# amebot_sensors.net
KiCad netlist of a schematic drawn in EAGLE
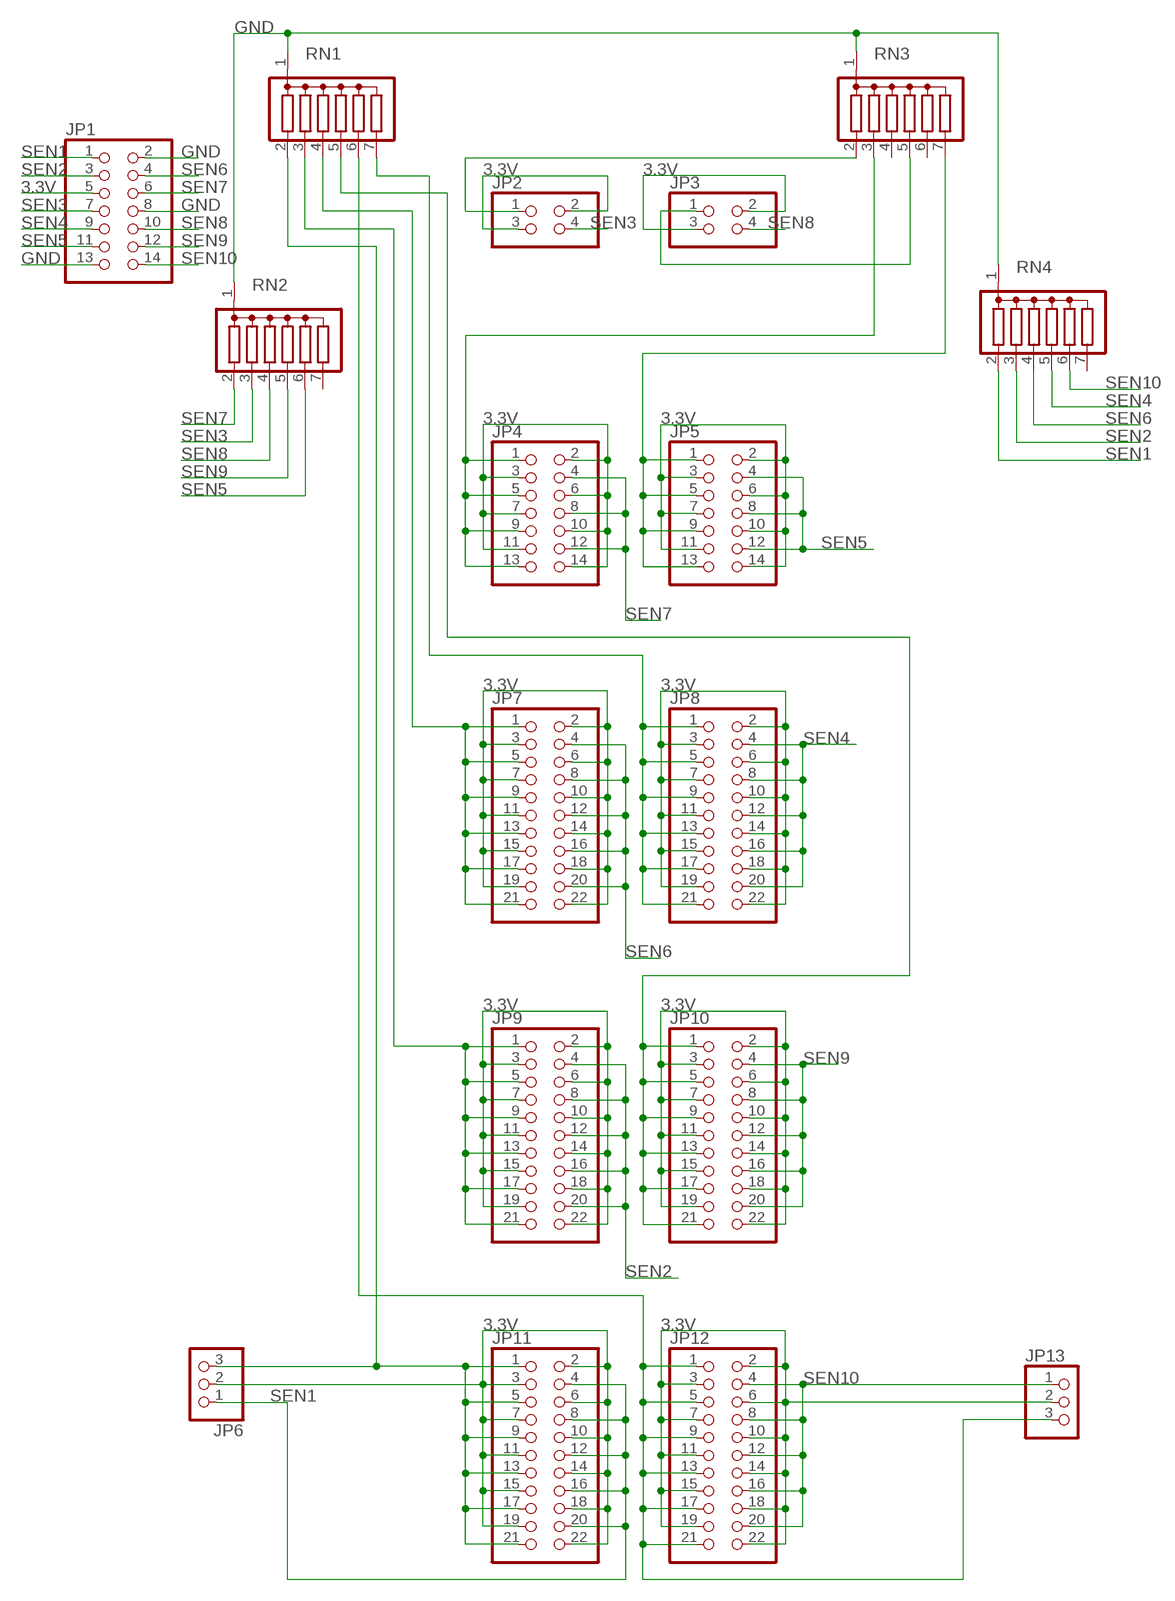
[diagram p0: schematic, sheet 1]

(export (version "E")
  (design (tool "Eeschema 10.0.6"))
  (components
    (comp (ref "JP1")
      (value "PINHD-2X7")
      (footprint "eagle-import:2X07")
      (libsource (lib "eagle-import") (part "PINHD-2X7"))
    )
    (comp (ref "JP2")
      (value "PINHD-2X2")
      (footprint "eagle-import:2X02")
      (libsource (lib "eagle-import") (part "PINHD-2X2"))
    )
    (comp (ref "JP3")
      (value "PINHD-2X2")
      (footprint "eagle-import:2X02")
      (libsource (lib "eagle-import") (part "PINHD-2X2"))
    )
    (comp (ref "JP4")
      (value "PINHD-2X7")
      (footprint "eagle-import:2X07")
      (libsource (lib "eagle-import") (part "PINHD-2X7"))
    )
    (comp (ref "JP5")
      (value "PINHD-2X7")
      (footprint "eagle-import:2X07")
      (libsource (lib "eagle-import") (part "PINHD-2X7"))
    )
    (comp (ref "JP6")
      (value "PINHD-1X3")
      (footprint "eagle-import:1X03")
      (libsource (lib "eagle-import") (part "PINHD-1X3"))
    )
    (comp (ref "JP7")
      (value "PINHD-2X11")
      (footprint "eagle-import:2X11")
      (libsource (lib "eagle-import") (part "PINHD-2X11"))
    )
    (comp (ref "JP8")
      (value "PINHD-2X11")
      (footprint "eagle-import:2X11")
      (libsource (lib "eagle-import") (part "PINHD-2X11"))
    )
    (comp (ref "JP9")
      (value "PINHD-2X11")
      (footprint "eagle-import:2X11")
      (libsource (lib "eagle-import") (part "PINHD-2X11"))
    )
    (comp (ref "JP10")
      (value "PINHD-2X11")
      (footprint "eagle-import:2X11")
      (libsource (lib "eagle-import") (part "PINHD-2X11"))
    )
    (comp (ref "JP11")
      (value "PINHD-2X11")
      (footprint "eagle-import:2X11")
      (libsource (lib "eagle-import") (part "PINHD-2X11"))
    )
    (comp (ref "JP12")
      (value "PINHD-2X11")
      (footprint "eagle-import:2X11")
      (libsource (lib "eagle-import") (part "PINHD-2X11"))
    )
    (comp (ref "JP13")
      (value "PINHD-1X3")
      (footprint "eagle-import:1X03")
      (libsource (lib "eagle-import") (part "PINHD-1X3"))
    )
    (comp (ref "RN1")
      (value "G06R")
      (footprint "eagle-import:SIL7")
      (libsource (lib "eagle-import") (part "G06R"))
    )
    (comp (ref "RN2")
      (value "G06R")
      (footprint "eagle-import:SIL7")
      (libsource (lib "eagle-import") (part "G06R"))
    )
    (comp (ref "RN3")
      (value "G06R")
      (footprint "eagle-import:SIL7")
      (libsource (lib "eagle-import") (part "G06R"))
    )
    (comp (ref "RN4")
      (value "G06R")
      (footprint "eagle-import:SIL7")
      (libsource (lib "eagle-import") (part "G06R"))
    )
  )
  (nets
    (net (code "1") (name "/3.3V") (class "Default")
      (node (ref "JP1") (pin "5") (pinfunction "5_5") (pintype "passive"))
      (node (ref "JP10") (pin "10") (pinfunction "10_10") (pintype "passive"))
      (node (ref "JP10") (pin "11") (pinfunction "11_11") (pintype "passive"))
      (node (ref "JP10") (pin "14") (pinfunction "14_14") (pintype "passive"))
      (node (ref "JP10") (pin "15") (pinfunction "15_15") (pintype "passive"))
      (node (ref "JP10") (pin "18") (pinfunction "18_18") (pintype "passive"))
      (node (ref "JP10") (pin "19") (pinfunction "19_19") (pintype "passive"))
      (node (ref "JP10") (pin "2") (pinfunction "2_2") (pintype "passive"))
      (node (ref "JP10") (pin "22") (pinfunction "22_22") (pintype "passive"))
      (node (ref "JP10") (pin "3") (pinfunction "3_3") (pintype "passive"))
      (node (ref "JP10") (pin "6") (pinfunction "6_6") (pintype "passive"))
      (node (ref "JP10") (pin "7") (pinfunction "7_7") (pintype "passive"))
      (node (ref "JP11") (pin "10") (pinfunction "10_10") (pintype "passive"))
      (node (ref "JP11") (pin "11") (pinfunction "11_11") (pintype "passive"))
      (node (ref "JP11") (pin "14") (pinfunction "14_14") (pintype "passive"))
      (node (ref "JP11") (pin "15") (pinfunction "15_15") (pintype "passive"))
      (node (ref "JP11") (pin "18") (pinfunction "18_18") (pintype "passive"))
      (node (ref "JP11") (pin "19") (pinfunction "19_19") (pintype "passive"))
      (node (ref "JP11") (pin "2") (pinfunction "2_2") (pintype "passive"))
      (node (ref "JP11") (pin "22") (pinfunction "22_22") (pintype "passive"))
      (node (ref "JP11") (pin "3") (pinfunction "3_3") (pintype "passive"))
      (node (ref "JP11") (pin "6") (pinfunction "6_6") (pintype "passive"))
      (node (ref "JP11") (pin "7") (pinfunction "7_7") (pintype "passive"))
      (node (ref "JP12") (pin "10") (pinfunction "10_10") (pintype "passive"))
      (node (ref "JP12") (pin "11") (pinfunction "11_11") (pintype "passive"))
      (node (ref "JP12") (pin "14") (pinfunction "14_14") (pintype "passive"))
      (node (ref "JP12") (pin "15") (pinfunction "15_15") (pintype "passive"))
      (node (ref "JP12") (pin "18") (pinfunction "18_18") (pintype "passive"))
      (node (ref "JP12") (pin "19") (pinfunction "19_19") (pintype "passive"))
      (node (ref "JP12") (pin "2") (pinfunction "2_2") (pintype "passive"))
      (node (ref "JP12") (pin "22") (pinfunction "22_22") (pintype "passive"))
      (node (ref "JP12") (pin "3") (pinfunction "3_3") (pintype "passive"))
      (node (ref "JP12") (pin "6") (pinfunction "6_6") (pintype "passive"))
      (node (ref "JP12") (pin "7") (pinfunction "7_7") (pintype "passive"))
      (node (ref "JP13") (pin "2") (pinfunction "2_2") (pintype "passive"))
      (node (ref "JP2") (pin "2") (pinfunction "2_2") (pintype "passive"))
      (node (ref "JP2") (pin "3") (pinfunction "3_3") (pintype "passive"))
      (node (ref "JP3") (pin "2") (pinfunction "2_2") (pintype "passive"))
      (node (ref "JP3") (pin "3") (pinfunction "3_3") (pintype "passive"))
      (node (ref "JP4") (pin "10") (pinfunction "10_10") (pintype "passive"))
      (node (ref "JP4") (pin "11") (pinfunction "11_11") (pintype "passive"))
      (node (ref "JP4") (pin "14") (pinfunction "14_14") (pintype "passive"))
      (node (ref "JP4") (pin "2") (pinfunction "2_2") (pintype "passive"))
      (node (ref "JP4") (pin "3") (pinfunction "3_3") (pintype "passive"))
      (node (ref "JP4") (pin "6") (pinfunction "6_6") (pintype "passive"))
      (node (ref "JP4") (pin "7") (pinfunction "7_7") (pintype "passive"))
      (node (ref "JP5") (pin "10") (pinfunction "10_10") (pintype "passive"))
      (node (ref "JP5") (pin "11") (pinfunction "11_11") (pintype "passive"))
      (node (ref "JP5") (pin "14") (pinfunction "14_14") (pintype "passive"))
      (node (ref "JP5") (pin "2") (pinfunction "2_2") (pintype "passive"))
      (node (ref "JP5") (pin "3") (pinfunction "3_3") (pintype "passive"))
      (node (ref "JP5") (pin "6") (pinfunction "6_6") (pintype "passive"))
      (node (ref "JP5") (pin "7") (pinfunction "7_7") (pintype "passive"))
      (node (ref "JP6") (pin "2") (pinfunction "2_2") (pintype "passive"))
      (node (ref "JP7") (pin "10") (pinfunction "10_10") (pintype "passive"))
      (node (ref "JP7") (pin "11") (pinfunction "11_11") (pintype "passive"))
      (node (ref "JP7") (pin "14") (pinfunction "14_14") (pintype "passive"))
      (node (ref "JP7") (pin "15") (pinfunction "15_15") (pintype "passive"))
      (node (ref "JP7") (pin "18") (pinfunction "18_18") (pintype "passive"))
      (node (ref "JP7") (pin "19") (pinfunction "19_19") (pintype "passive"))
      (node (ref "JP7") (pin "2") (pinfunction "2_2") (pintype "passive"))
      (node (ref "JP7") (pin "22") (pinfunction "22_22") (pintype "passive"))
      (node (ref "JP7") (pin "3") (pinfunction "3_3") (pintype "passive"))
      (node (ref "JP7") (pin "6") (pinfunction "6_6") (pintype "passive"))
      (node (ref "JP7") (pin "7") (pinfunction "7_7") (pintype "passive"))
      (node (ref "JP8") (pin "10") (pinfunction "10_10") (pintype "passive"))
      (node (ref "JP8") (pin "11") (pinfunction "11_11") (pintype "passive"))
      (node (ref "JP8") (pin "14") (pinfunction "14_14") (pintype "passive"))
      (node (ref "JP8") (pin "15") (pinfunction "15_15") (pintype "passive"))
      (node (ref "JP8") (pin "18") (pinfunction "18_18") (pintype "passive"))
      (node (ref "JP8") (pin "19") (pinfunction "19_19") (pintype "passive"))
      (node (ref "JP8") (pin "2") (pinfunction "2_2") (pintype "passive"))
      (node (ref "JP8") (pin "22") (pinfunction "22_22") (pintype "passive"))
      (node (ref "JP8") (pin "3") (pinfunction "3_3") (pintype "passive"))
      (node (ref "JP8") (pin "6") (pinfunction "6_6") (pintype "passive"))
      (node (ref "JP8") (pin "7") (pinfunction "7_7") (pintype "passive"))
      (node (ref "JP9") (pin "10") (pinfunction "10_10") (pintype "passive"))
      (node (ref "JP9") (pin "11") (pinfunction "11_11") (pintype "passive"))
      (node (ref "JP9") (pin "14") (pinfunction "14_14") (pintype "passive"))
      (node (ref "JP9") (pin "15") (pinfunction "15_15") (pintype "passive"))
      (node (ref "JP9") (pin "18") (pinfunction "18_18") (pintype "passive"))
      (node (ref "JP9") (pin "19") (pinfunction "19_19") (pintype "passive"))
      (node (ref "JP9") (pin "2") (pinfunction "2_2") (pintype "passive"))
      (node (ref "JP9") (pin "22") (pinfunction "22_22") (pintype "passive"))
      (node (ref "JP9") (pin "3") (pinfunction "3_3") (pintype "passive"))
      (node (ref "JP9") (pin "6") (pinfunction "6_6") (pintype "passive"))
      (node (ref "JP9") (pin "7") (pinfunction "7_7") (pintype "passive"))
    )
    (net (code "2") (name "/GND") (class "Default")
      (node (ref "JP1") (pin "13") (pinfunction "13_13") (pintype "passive"))
      (node (ref "JP1") (pin "2") (pinfunction "2_2") (pintype "passive"))
      (node (ref "JP1") (pin "8") (pinfunction "8_8") (pintype "passive"))
      (node (ref "RN1") (pin "1") (pinfunction "1_1") (pintype "passive"))
      (node (ref "RN2") (pin "1") (pinfunction "1_1") (pintype "passive"))
      (node (ref "RN3") (pin "1") (pinfunction "1_1") (pintype "passive"))
      (node (ref "RN4") (pin "1") (pinfunction "1_1") (pintype "passive"))
    )
    (net (code "3") (name "/SEN1") (class "Default")
      (node (ref "JP1") (pin "1") (pinfunction "1_1") (pintype "passive"))
      (node (ref "JP11") (pin "12") (pinfunction "12_12") (pintype "passive"))
      (node (ref "JP11") (pin "16") (pinfunction "16_16") (pintype "passive"))
      (node (ref "JP11") (pin "20") (pinfunction "20_20") (pintype "passive"))
      (node (ref "JP11") (pin "4") (pinfunction "4_4") (pintype "passive"))
      (node (ref "JP11") (pin "8") (pinfunction "8_8") (pintype "passive"))
      (node (ref "JP6") (pin "1") (pinfunction "1_1") (pintype "passive"))
      (node (ref "RN4") (pin "2") (pinfunction "2_2") (pintype "passive"))
    )
    (net (code "4") (name "/SEN2") (class "Default")
      (node (ref "JP1") (pin "3") (pinfunction "3_3") (pintype "passive"))
      (node (ref "JP9") (pin "12") (pinfunction "12_12") (pintype "passive"))
      (node (ref "JP9") (pin "16") (pinfunction "16_16") (pintype "passive"))
      (node (ref "JP9") (pin "20") (pinfunction "20_20") (pintype "passive"))
      (node (ref "JP9") (pin "4") (pinfunction "4_4") (pintype "passive"))
      (node (ref "JP9") (pin "8") (pinfunction "8_8") (pintype "passive"))
      (node (ref "RN4") (pin "3") (pinfunction "3_3") (pintype "passive"))
    )
    (net (code "5") (name "/SEN3") (class "Default")
      (node (ref "JP1") (pin "7") (pinfunction "7_7") (pintype "passive"))
      (node (ref "JP2") (pin "4") (pinfunction "4_4") (pintype "passive"))
      (node (ref "RN2") (pin "3") (pinfunction "3_3") (pintype "passive"))
    )
    (net (code "6") (name "/SEN4") (class "Default")
      (node (ref "JP1") (pin "9") (pinfunction "9_9") (pintype "passive"))
      (node (ref "JP8") (pin "12") (pinfunction "12_12") (pintype "passive"))
      (node (ref "JP8") (pin "16") (pinfunction "16_16") (pintype "passive"))
      (node (ref "JP8") (pin "20") (pinfunction "20_20") (pintype "passive"))
      (node (ref "JP8") (pin "4") (pinfunction "4_4") (pintype "passive"))
      (node (ref "JP8") (pin "8") (pinfunction "8_8") (pintype "passive"))
      (node (ref "RN4") (pin "5") (pinfunction "5_5") (pintype "passive"))
    )
    (net (code "7") (name "/SEN5") (class "Default")
      (node (ref "JP1") (pin "11") (pinfunction "11_11") (pintype "passive"))
      (node (ref "JP5") (pin "12") (pinfunction "12_12") (pintype "passive"))
      (node (ref "JP5") (pin "4") (pinfunction "4_4") (pintype "passive"))
      (node (ref "JP5") (pin "8") (pinfunction "8_8") (pintype "passive"))
      (node (ref "RN2") (pin "6") (pinfunction "6_6") (pintype "passive"))
    )
    (net (code "8") (name "/SEN6") (class "Default")
      (node (ref "JP1") (pin "4") (pinfunction "4_4") (pintype "passive"))
      (node (ref "JP7") (pin "12") (pinfunction "12_12") (pintype "passive"))
      (node (ref "JP7") (pin "16") (pinfunction "16_16") (pintype "passive"))
      (node (ref "JP7") (pin "20") (pinfunction "20_20") (pintype "passive"))
      (node (ref "JP7") (pin "4") (pinfunction "4_4") (pintype "passive"))
      (node (ref "JP7") (pin "8") (pinfunction "8_8") (pintype "passive"))
      (node (ref "RN4") (pin "4") (pinfunction "4_4") (pintype "passive"))
    )
    (net (code "9") (name "/SEN7") (class "Default")
      (node (ref "JP1") (pin "6") (pinfunction "6_6") (pintype "passive"))
      (node (ref "JP4") (pin "12") (pinfunction "12_12") (pintype "passive"))
      (node (ref "JP4") (pin "4") (pinfunction "4_4") (pintype "passive"))
      (node (ref "JP4") (pin "8") (pinfunction "8_8") (pintype "passive"))
      (node (ref "RN2") (pin "2") (pinfunction "2_2") (pintype "passive"))
    )
    (net (code "10") (name "/SEN8") (class "Default")
      (node (ref "JP1") (pin "10") (pinfunction "10_10") (pintype "passive"))
      (node (ref "JP3") (pin "4") (pinfunction "4_4") (pintype "passive"))
      (node (ref "RN2") (pin "4") (pinfunction "4_4") (pintype "passive"))
    )
    (net (code "11") (name "/SEN9") (class "Default")
      (node (ref "JP1") (pin "12") (pinfunction "12_12") (pintype "passive"))
      (node (ref "JP10") (pin "12") (pinfunction "12_12") (pintype "passive"))
      (node (ref "JP10") (pin "16") (pinfunction "16_16") (pintype "passive"))
      (node (ref "JP10") (pin "20") (pinfunction "20_20") (pintype "passive"))
      (node (ref "JP10") (pin "4") (pinfunction "4_4") (pintype "passive"))
      (node (ref "JP10") (pin "8") (pinfunction "8_8") (pintype "passive"))
      (node (ref "RN2") (pin "5") (pinfunction "5_5") (pintype "passive"))
    )
    (net (code "12") (name "/SEN10") (class "Default")
      (node (ref "JP1") (pin "14") (pinfunction "14_14") (pintype "passive"))
      (node (ref "JP12") (pin "12") (pinfunction "12_12") (pintype "passive"))
      (node (ref "JP12") (pin "16") (pinfunction "16_16") (pintype "passive"))
      (node (ref "JP12") (pin "20") (pinfunction "20_20") (pintype "passive"))
      (node (ref "JP12") (pin "4") (pinfunction "4_4") (pintype "passive"))
      (node (ref "JP12") (pin "8") (pinfunction "8_8") (pintype "passive"))
      (node (ref "JP13") (pin "1") (pinfunction "1_1") (pintype "passive"))
      (node (ref "RN4") (pin "6") (pinfunction "6_6") (pintype "passive"))
    )
    (net (code "13") (name "Net-(JP2-Pad1)") (class "Default")
      (node (ref "JP2") (pin "1") (pinfunction "1_1") (pintype "passive"))
      (node (ref "RN3") (pin "2") (pinfunction "2_2") (pintype "passive"))
    )
    (net (code "14") (name "Net-(JP3-Pad1)") (class "Default")
      (node (ref "JP3") (pin "1") (pinfunction "1_1") (pintype "passive"))
      (node (ref "RN3") (pin "5") (pinfunction "5_5") (pintype "passive"))
    )
    (net (code "15") (name "Net-(JP4-Pad1)") (class "Default")
      (node (ref "JP4") (pin "1") (pinfunction "1_1") (pintype "passive"))
      (node (ref "JP4") (pin "13") (pinfunction "13_13") (pintype "passive"))
      (node (ref "JP4") (pin "5") (pinfunction "5_5") (pintype "passive"))
      (node (ref "JP4") (pin "9") (pinfunction "9_9") (pintype "passive"))
      (node (ref "RN3") (pin "3") (pinfunction "3_3") (pintype "passive"))
    )
    (net (code "16") (name "Net-(JP5-Pad1)") (class "Default")
      (node (ref "JP5") (pin "1") (pinfunction "1_1") (pintype "passive"))
      (node (ref "JP5") (pin "13") (pinfunction "13_13") (pintype "passive"))
      (node (ref "JP5") (pin "5") (pinfunction "5_5") (pintype "passive"))
      (node (ref "JP5") (pin "9") (pinfunction "9_9") (pintype "passive"))
      (node (ref "RN3") (pin "7") (pinfunction "7_7") (pintype "passive"))
    )
    (net (code "17") (name "Net-(JP7-Pad1)") (class "Default")
      (node (ref "JP7") (pin "1") (pinfunction "1_1") (pintype "passive"))
      (node (ref "JP7") (pin "13") (pinfunction "13_13") (pintype "passive"))
      (node (ref "JP7") (pin "17") (pinfunction "17_17") (pintype "passive"))
      (node (ref "JP7") (pin "21") (pinfunction "21_21") (pintype "passive"))
      (node (ref "JP7") (pin "5") (pinfunction "5_5") (pintype "passive"))
      (node (ref "JP7") (pin "9") (pinfunction "9_9") (pintype "passive"))
      (node (ref "RN1") (pin "4") (pinfunction "4_4") (pintype "passive"))
    )
    (net (code "18") (name "Net-(JP8-Pad1)") (class "Default")
      (node (ref "JP8") (pin "1") (pinfunction "1_1") (pintype "passive"))
      (node (ref "JP8") (pin "13") (pinfunction "13_13") (pintype "passive"))
      (node (ref "JP8") (pin "17") (pinfunction "17_17") (pintype "passive"))
      (node (ref "JP8") (pin "21") (pinfunction "21_21") (pintype "passive"))
      (node (ref "JP8") (pin "5") (pinfunction "5_5") (pintype "passive"))
      (node (ref "JP8") (pin "9") (pinfunction "9_9") (pintype "passive"))
      (node (ref "RN1") (pin "7") (pinfunction "7_7") (pintype "passive"))
    )
    (net (code "19") (name "Net-(JP9-Pad1)") (class "Default")
      (node (ref "JP9") (pin "1") (pinfunction "1_1") (pintype "passive"))
      (node (ref "JP9") (pin "13") (pinfunction "13_13") (pintype "passive"))
      (node (ref "JP9") (pin "17") (pinfunction "17_17") (pintype "passive"))
      (node (ref "JP9") (pin "21") (pinfunction "21_21") (pintype "passive"))
      (node (ref "JP9") (pin "5") (pinfunction "5_5") (pintype "passive"))
      (node (ref "JP9") (pin "9") (pinfunction "9_9") (pintype "passive"))
      (node (ref "RN1") (pin "3") (pinfunction "3_3") (pintype "passive"))
    )
    (net (code "20") (name "Net-(JP10-Pad1)") (class "Default")
      (node (ref "JP10") (pin "1") (pinfunction "1_1") (pintype "passive"))
      (node (ref "JP10") (pin "13") (pinfunction "13_13") (pintype "passive"))
      (node (ref "JP10") (pin "17") (pinfunction "17_17") (pintype "passive"))
      (node (ref "JP10") (pin "21") (pinfunction "21_21") (pintype "passive"))
      (node (ref "JP10") (pin "5") (pinfunction "5_5") (pintype "passive"))
      (node (ref "JP10") (pin "9") (pinfunction "9_9") (pintype "passive"))
      (node (ref "RN1") (pin "5") (pinfunction "5_5") (pintype "passive"))
    )
    (net (code "21") (name "Net-(JP11-Pad1)") (class "Default")
      (node (ref "JP11") (pin "1") (pinfunction "1_1") (pintype "passive"))
      (node (ref "JP11") (pin "13") (pinfunction "13_13") (pintype "passive"))
      (node (ref "JP11") (pin "17") (pinfunction "17_17") (pintype "passive"))
      (node (ref "JP11") (pin "21") (pinfunction "21_21") (pintype "passive"))
      (node (ref "JP11") (pin "5") (pinfunction "5_5") (pintype "passive"))
      (node (ref "JP11") (pin "9") (pinfunction "9_9") (pintype "passive"))
      (node (ref "JP6") (pin "3") (pinfunction "3_3") (pintype "passive"))
      (node (ref "RN1") (pin "2") (pinfunction "2_2") (pintype "passive"))
    )
    (net (code "22") (name "Net-(JP12-Pad1)") (class "Default")
      (node (ref "JP12") (pin "1") (pinfunction "1_1") (pintype "passive"))
      (node (ref "JP12") (pin "13") (pinfunction "13_13") (pintype "passive"))
      (node (ref "JP12") (pin "17") (pinfunction "17_17") (pintype "passive"))
      (node (ref "JP12") (pin "21") (pinfunction "21_21") (pintype "passive"))
      (node (ref "JP12") (pin "5") (pinfunction "5_5") (pintype "passive"))
      (node (ref "JP12") (pin "9") (pinfunction "9_9") (pintype "passive"))
      (node (ref "JP13") (pin "3") (pinfunction "3_3") (pintype "passive"))
      (node (ref "RN1") (pin "6") (pinfunction "6_6") (pintype "passive"))
    )
    (net (code "23") (name "unconnected-(RN2-Pad7)") (class "Default")
      (node (ref "RN2") (pin "7") (pinfunction "7_7") (pintype "passive"))
    )
    (net (code "24") (name "unconnected-(RN3-Pad4)") (class "Default")
      (node (ref "RN3") (pin "4") (pinfunction "4_4") (pintype "passive"))
    )
    (net (code "25") (name "unconnected-(RN3-Pad6)") (class "Default")
      (node (ref "RN3") (pin "6") (pinfunction "6_6") (pintype "passive"))
    )
    (net (code "26") (name "unconnected-(RN4-Pad7)") (class "Default")
      (node (ref "RN4") (pin "7") (pinfunction "7_7") (pintype "passive"))
    )
  )
)
